# SCH_UsbHub_2024-08-12.net
KiCad netlist of a schematic drawn in EasyEDA
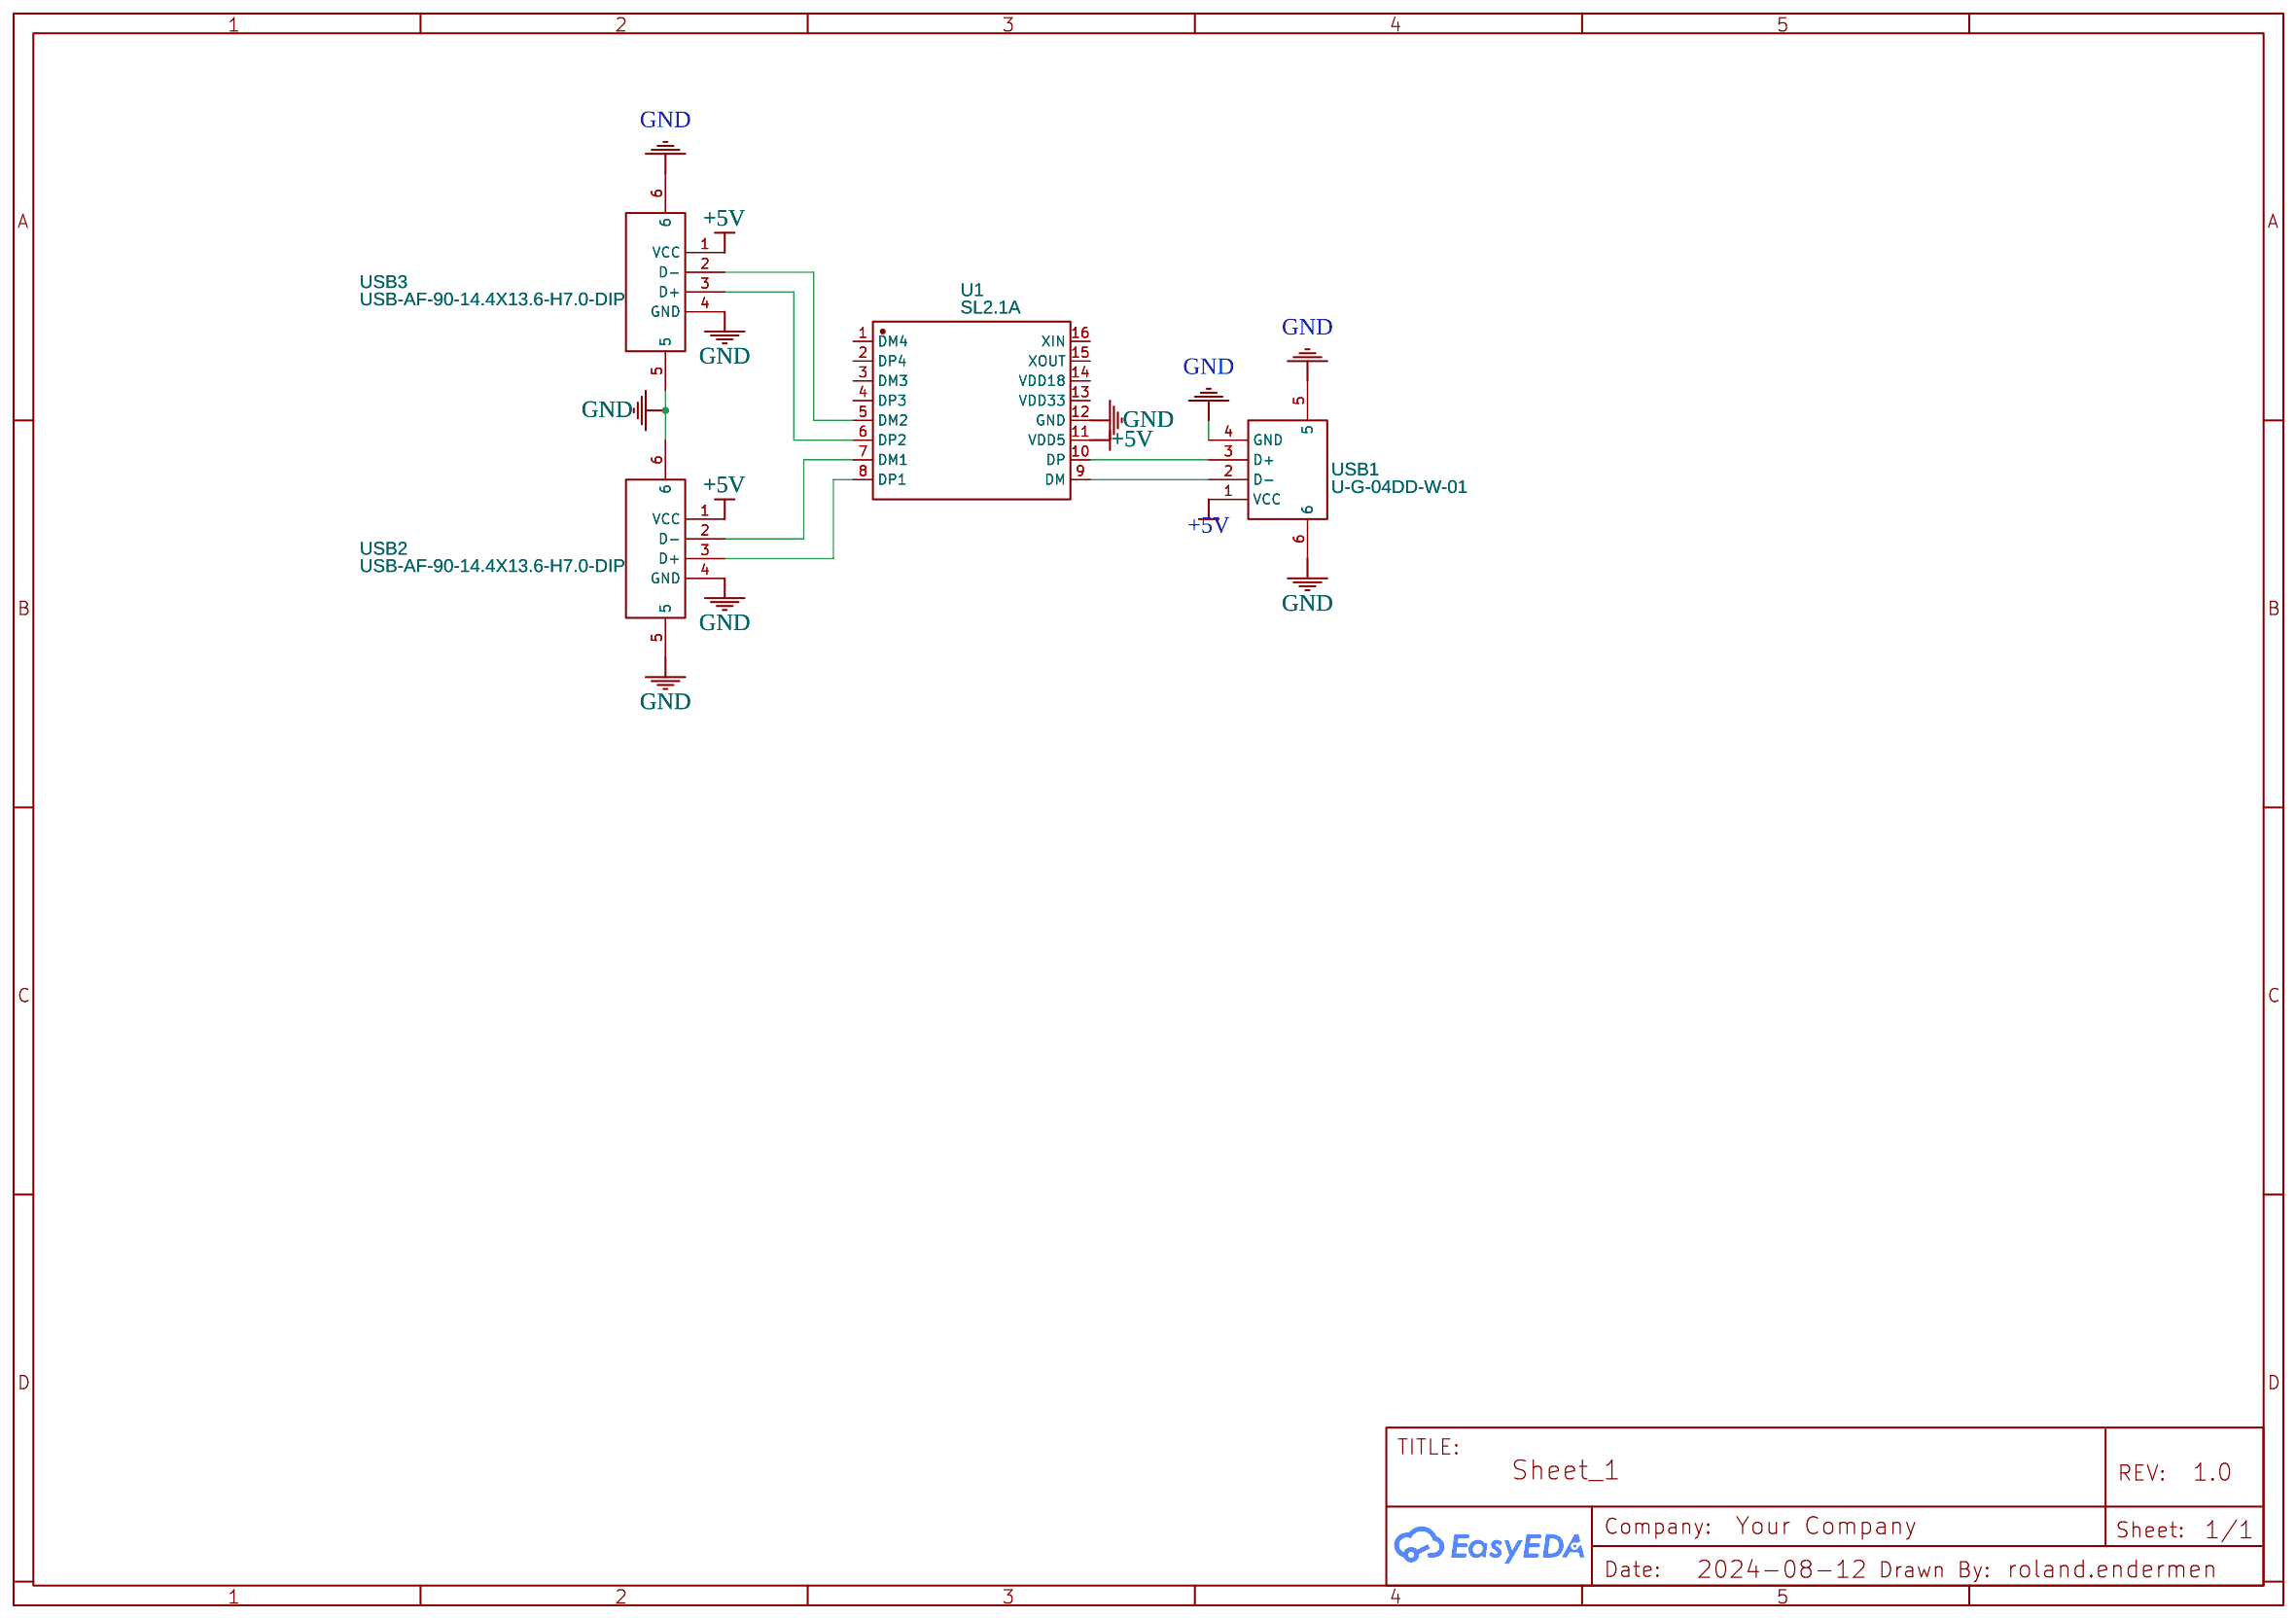
[diagram p0: schematic sheet]

(export (version "E")
  (design (tool "Eeschema 10.0.6"))
  (components
    (comp (ref "U1")
      (value "SL2.1A")
      (fields (field (name "Manufacturer") "CoreChips(和芯润德)"))
      (libsource (lib "") (part "SL2.1A"))
    )
    (comp (ref "USB1")
      (value "U-G-04DD-W-01")
      (fields (field (name "Manufacturer Part") "U-G-O4DD-W-1") (field (name "Manufacturer") "韩国韩荣"))
      (libsource (lib "") (part "U-G-04DD-W-01"))
    )
    (comp (ref "USB2")
      (value "USB-AF-90-14.4X13.6-H7.0-DIP")
      (fields (field (name "Manufacturer Part") "903-131A1011D10100") (field (name "Manufacturer") "精拓金"))
      (libsource (lib "") (part "USB-AF-90-14.4X13.6-H7.0-DIP"))
    )
    (comp (ref "USB3")
      (value "USB-AF-90-14.4X13.6-H7.0-DIP")
      (fields (field (name "Manufacturer Part") "903-131A1011D10100") (field (name "Manufacturer") "精拓金"))
      (libsource (lib "") (part "USB-AF-90-14.4X13.6-H7.0-DIP"))
    )
  )
  (nets
    (net (code "1") (name "+5V") (class "Default")
      (node (ref "U1") (pin "11") (pinfunction "VDD5_11") (pintype "unspecified"))
      (node (ref "USB1") (pin "1") (pinfunction "VCC_1") (pintype "unspecified"))
      (node (ref "USB2") (pin "1") (pinfunction "VCC_1") (pintype "unspecified"))
      (node (ref "USB3") (pin "1") (pinfunction "VCC_1") (pintype "unspecified"))
    )
    (net (code "2") (name "GND") (class "Default")
      (node (ref "U1") (pin "12") (pinfunction "GND_12") (pintype "unspecified"))
      (node (ref "USB1") (pin "4") (pinfunction "GND_4") (pintype "unspecified"))
      (node (ref "USB1") (pin "5") (pinfunction "5_5") (pintype "unspecified"))
      (node (ref "USB1") (pin "6") (pinfunction "6_6") (pintype "unspecified"))
      (node (ref "USB2") (pin "4") (pinfunction "GND_4") (pintype "unspecified"))
      (node (ref "USB2") (pin "5") (pinfunction "5_5") (pintype "unspecified"))
      (node (ref "USB2") (pin "6") (pinfunction "6_6") (pintype "unspecified"))
      (node (ref "USB3") (pin "4") (pinfunction "GND_4") (pintype "unspecified"))
      (node (ref "USB3") (pin "5") (pinfunction "5_5") (pintype "unspecified"))
      (node (ref "USB3") (pin "6") (pinfunction "6_6") (pintype "unspecified"))
    )
    (net (code "3") (name "Net-(U1-DM)") (class "Default")
      (node (ref "U1") (pin "9") (pinfunction "DM_9") (pintype "unspecified"))
      (node (ref "USB1") (pin "2") (pinfunction "D-_2") (pintype "unspecified"))
    )
    (net (code "4") (name "Net-(U1-DM1)") (class "Default")
      (node (ref "U1") (pin "7") (pinfunction "DM1_7") (pintype "unspecified"))
      (node (ref "USB2") (pin "2") (pinfunction "D-_2") (pintype "unspecified"))
    )
    (net (code "5") (name "Net-(U1-DM2)") (class "Default")
      (node (ref "U1") (pin "5") (pinfunction "DM2_5") (pintype "unspecified"))
      (node (ref "USB3") (pin "2") (pinfunction "D-_2") (pintype "unspecified"))
    )
    (net (code "6") (name "Net-(U1-DP)") (class "Default")
      (node (ref "U1") (pin "10") (pinfunction "DP_10") (pintype "unspecified"))
      (node (ref "USB1") (pin "3") (pinfunction "D+_3") (pintype "unspecified"))
    )
    (net (code "7") (name "Net-(U1-DP1)") (class "Default")
      (node (ref "U1") (pin "8") (pinfunction "DP1_8") (pintype "unspecified"))
      (node (ref "USB2") (pin "3") (pinfunction "D+_3") (pintype "unspecified"))
    )
    (net (code "8") (name "Net-(U1-DP2)") (class "Default")
      (node (ref "U1") (pin "6") (pinfunction "DP2_6") (pintype "unspecified"))
      (node (ref "USB3") (pin "3") (pinfunction "D+_3") (pintype "unspecified"))
    )
    (net (code "9") (name "unconnected-(U1-DM3-Pad3)") (class "Default")
      (node (ref "U1") (pin "3") (pinfunction "DM3_3") (pintype "unspecified"))
    )
    (net (code "10") (name "unconnected-(U1-DM4-Pad1)") (class "Default")
      (node (ref "U1") (pin "1") (pinfunction "DM4_1") (pintype "unspecified"))
    )
    (net (code "11") (name "unconnected-(U1-DP3-Pad4)") (class "Default")
      (node (ref "U1") (pin "4") (pinfunction "DP3_4") (pintype "unspecified"))
    )
    (net (code "12") (name "unconnected-(U1-DP4-Pad2)") (class "Default")
      (node (ref "U1") (pin "2") (pinfunction "DP4_2") (pintype "unspecified"))
    )
    (net (code "13") (name "unconnected-(U1-VDD18-Pad14)") (class "Default")
      (node (ref "U1") (pin "14") (pinfunction "VDD18_14") (pintype "unspecified"))
    )
    (net (code "14") (name "unconnected-(U1-VDD33-Pad13)") (class "Default")
      (node (ref "U1") (pin "13") (pinfunction "VDD33_13") (pintype "unspecified"))
    )
    (net (code "15") (name "unconnected-(U1-XIN-Pad16)") (class "Default")
      (node (ref "U1") (pin "16") (pinfunction "XIN_16") (pintype "unspecified"))
    )
    (net (code "16") (name "unconnected-(U1-XOUT-Pad15)") (class "Default")
      (node (ref "U1") (pin "15") (pinfunction "XOUT_15") (pintype "unspecified"))
    )
  )
)
